# LasCon.net
KiCad netlist of a schematic drawn in EAGLE
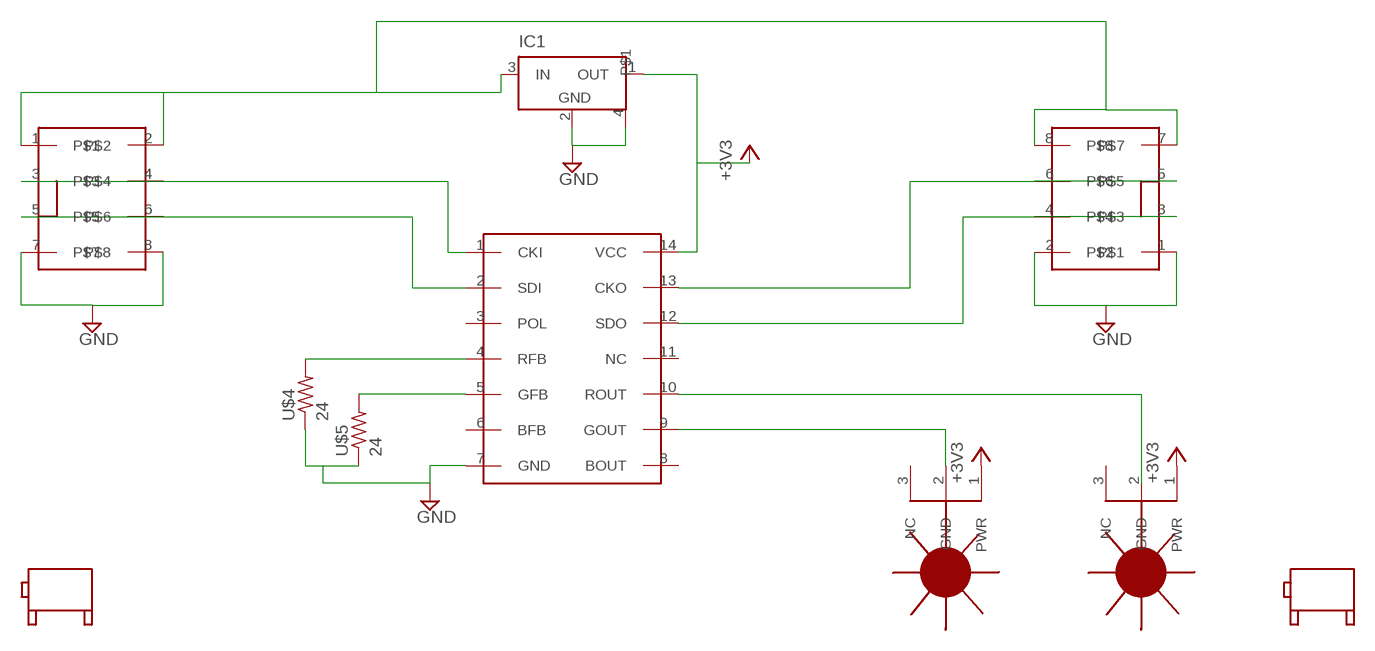
[diagram p0: schematic, sheet 1]

(export (version "E")
  (design (tool "Eeschema 10.0.6"))
  (components
    (comp (ref "IC1")
      (value "MCP1804T-3302I")
      (footprint "eagle-import:SOT223")
      (libsource (lib "eagle-import") (part "MCP1804T-3302I"))
    )
    (comp (ref "U$1")
      (value "2X4IDC")
      (footprint "eagle-import:2X04")
      (fields (field (name "MPN") "75869-132LF"))
      (libsource (lib "eagle-import") (part "2X4IDC"))
    )
    (comp (ref "U$2")
      (value "2X4IDC")
      (footprint "eagle-import:2X04")
      (fields (field (name "MPN") "75869-132LF"))
      (libsource (lib "eagle-import") (part "2X4IDC"))
    )
    (comp (ref "U$3")
      (value "WS2801")
      (footprint "eagle-import:SO14")
      (libsource (lib "eagle-import") (part "WS2801"))
    )
    (comp (ref "U$4")
      (value "24")
      (footprint "eagle-import:RF-C0805")
      (libsource (lib "eagle-import") (part "RF-R0805"))
    )
    (comp (ref "U$5")
      (value "24")
      (footprint "eagle-import:RF-C0805")
      (libsource (lib "eagle-import") (part "RF-R0805"))
    )
    (comp (ref "U$6")
      (value "LASER")
      (footprint "eagle-import:LASER")
      (libsource (lib "eagle-import") (part "LASER"))
    )
    (comp (ref "U$7")
      (value "LASER")
      (footprint "eagle-import:LASER")
      (libsource (lib "eagle-import") (part "LASER"))
    )
    (comp (ref "U$8")
      (value "90DEGMNT")
      (footprint "eagle-import:90DEGMNT")
      (libsource (lib "eagle-import") (part "90DEGMNT"))
    )
    (comp (ref "U$9")
      (value "90DEGMNT")
      (footprint "eagle-import:90DEGMNT")
      (libsource (lib "eagle-import") (part "90DEGMNT"))
    )
  )
  (nets
    (net (code "1") (name "+3V3") (class "Default")
      (node (ref "IC1") (pin "1") (pinfunction "OUT_1") (pintype "output"))
      (node (ref "U$3") (pin "14") (pinfunction "VCC_14") (pintype "bidirectional"))
      (node (ref "U$6") (pin "1") (pinfunction "PWR_1") (pintype "bidirectional"))
      (node (ref "U$7") (pin "1") (pinfunction "PWR_1") (pintype "bidirectional"))
    )
    (net (code "2") (name "GND") (class "Default")
      (node (ref "IC1") (pin "2") (pinfunction "GND_2") (pintype "power_in"))
      (node (ref "IC1") (pin "4") (pinfunction "P$1_4") (pintype "bidirectional"))
      (node (ref "U$1") (pin "7") (pinfunction "P$7_7") (pintype "bidirectional"))
      (node (ref "U$1") (pin "8") (pinfunction "P$8_8") (pintype "bidirectional"))
      (node (ref "U$2") (pin "1") (pinfunction "P$1_1") (pintype "bidirectional"))
      (node (ref "U$2") (pin "2") (pinfunction "P$2_2") (pintype "bidirectional"))
      (node (ref "U$3") (pin "7") (pinfunction "GND_7") (pintype "bidirectional"))
      (node (ref "U$4") (pin "1") (pinfunction "1_1") (pintype "passive"))
      (node (ref "U$5") (pin "1") (pinfunction "1_1") (pintype "passive"))
    )
    (net (code "3") (name "Net-(IC1-IN)") (class "Default")
      (node (ref "IC1") (pin "3") (pinfunction "IN_3") (pintype "input"))
      (node (ref "U$1") (pin "1") (pinfunction "P$1_1") (pintype "bidirectional"))
      (node (ref "U$1") (pin "2") (pinfunction "P$2_2") (pintype "bidirectional"))
      (node (ref "U$2") (pin "7") (pinfunction "P$7_7") (pintype "bidirectional"))
      (node (ref "U$2") (pin "8") (pinfunction "P$8_8") (pintype "bidirectional"))
    )
    (net (code "4") (name "Net-(U$1-P$3)") (class "Default")
      (node (ref "U$1") (pin "3") (pinfunction "P$3_3") (pintype "bidirectional"))
      (node (ref "U$1") (pin "4") (pinfunction "P$4_4") (pintype "bidirectional"))
      (node (ref "U$3") (pin "1") (pinfunction "CKI_1") (pintype "bidirectional"))
    )
    (net (code "5") (name "Net-(U$1-P$5)") (class "Default")
      (node (ref "U$1") (pin "5") (pinfunction "P$5_5") (pintype "bidirectional"))
      (node (ref "U$1") (pin "6") (pinfunction "P$6_6") (pintype "bidirectional"))
      (node (ref "U$3") (pin "2") (pinfunction "SDI_2") (pintype "bidirectional"))
    )
    (net (code "6") (name "Net-(U$2-P$3)") (class "Default")
      (node (ref "U$2") (pin "3") (pinfunction "P$3_3") (pintype "bidirectional"))
      (node (ref "U$2") (pin "4") (pinfunction "P$4_4") (pintype "bidirectional"))
      (node (ref "U$3") (pin "12") (pinfunction "SDO_12") (pintype "bidirectional"))
    )
    (net (code "7") (name "Net-(U$2-P$5)") (class "Default")
      (node (ref "U$2") (pin "5") (pinfunction "P$5_5") (pintype "bidirectional"))
      (node (ref "U$2") (pin "6") (pinfunction "P$6_6") (pintype "bidirectional"))
      (node (ref "U$3") (pin "13") (pinfunction "CKO_13") (pintype "bidirectional"))
    )
    (net (code "8") (name "Net-(U$3-GFB)") (class "Default")
      (node (ref "U$3") (pin "5") (pinfunction "GFB_5") (pintype "bidirectional"))
      (node (ref "U$5") (pin "2") (pinfunction "2_2") (pintype "passive"))
    )
    (net (code "9") (name "Net-(U$3-GOUT)") (class "Default")
      (node (ref "U$3") (pin "9") (pinfunction "GOUT_9") (pintype "bidirectional"))
      (node (ref "U$6") (pin "2") (pinfunction "GND_2") (pintype "bidirectional"))
    )
    (net (code "10") (name "Net-(U$3-RFB)") (class "Default")
      (node (ref "U$3") (pin "4") (pinfunction "RFB_4") (pintype "bidirectional"))
      (node (ref "U$4") (pin "2") (pinfunction "2_2") (pintype "passive"))
    )
    (net (code "11") (name "Net-(U$3-ROUT)") (class "Default")
      (node (ref "U$3") (pin "10") (pinfunction "ROUT_10") (pintype "bidirectional"))
      (node (ref "U$7") (pin "2") (pinfunction "GND_2") (pintype "bidirectional"))
    )
    (net (code "12") (name "unconnected-(U$3-BFB-Pad6)") (class "Default")
      (node (ref "U$3") (pin "6") (pinfunction "BFB_6") (pintype "bidirectional"))
    )
    (net (code "13") (name "unconnected-(U$3-BOUT-Pad8)") (class "Default")
      (node (ref "U$3") (pin "8") (pinfunction "BOUT_8") (pintype "bidirectional"))
    )
    (net (code "14") (name "unconnected-(U$3-NC-Pad11)") (class "Default")
      (node (ref "U$3") (pin "11") (pinfunction "NC_11") (pintype "bidirectional"))
    )
    (net (code "15") (name "unconnected-(U$3-POL-Pad3)") (class "Default")
      (node (ref "U$3") (pin "3") (pinfunction "POL_3") (pintype "bidirectional"))
    )
    (net (code "16") (name "unconnected-(U$6-NC-Pad3)") (class "Default")
      (node (ref "U$6") (pin "3") (pinfunction "NC_3") (pintype "bidirectional"))
    )
    (net (code "17") (name "unconnected-(U$7-NC-Pad3)") (class "Default")
      (node (ref "U$7") (pin "3") (pinfunction "NC_3") (pintype "bidirectional"))
    )
  )
)
